# I2C_matrix_V0_1.net
KiCad netlist of a schematic drawn in EAGLE
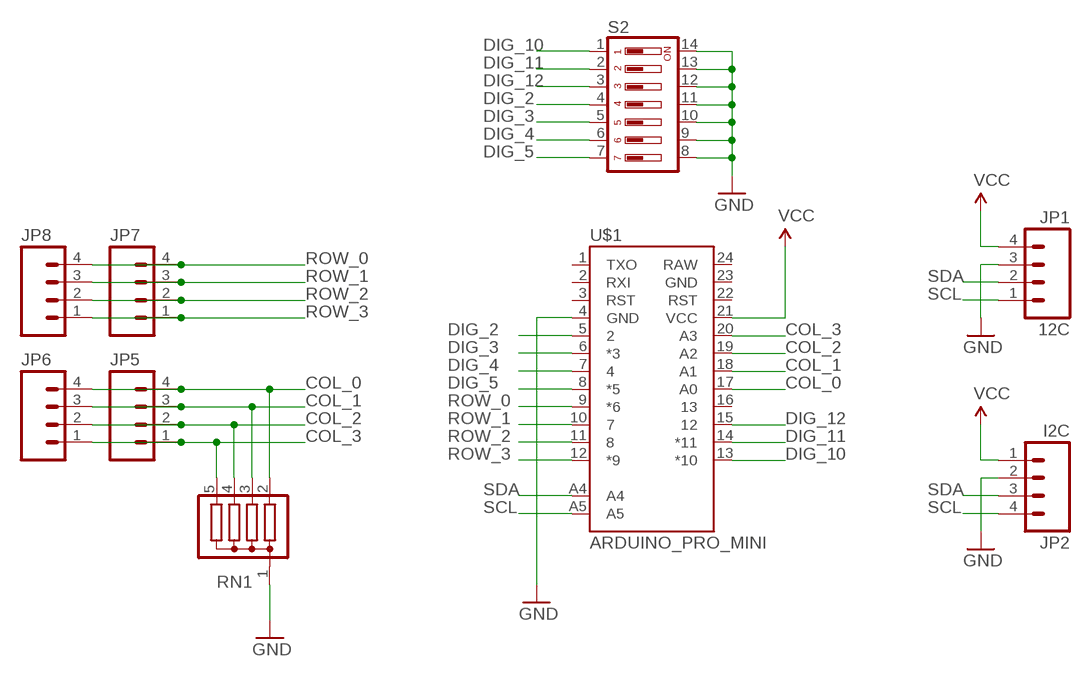
[diagram p0: schematic, sheet 1]

(export (version "E")
  (design (tool "Eeschema 10.0.6"))
  (components
    (comp (ref "JP1")
      (value "12C")
      (footprint "eagle-import:1X04-SMD_LONG")
      (libsource (lib "eagle-import") (part "M04SMD_LONG"))
    )
    (comp (ref "JP2")
      (value "I2C")
      (footprint "eagle-import:1X04-SMD_LONG")
      (libsource (lib "eagle-import") (part "M04SMD_LONG"))
    )
    (comp (ref "JP5")
      (value "M04LONGPADS")
      (footprint "eagle-import:1X04_LONGPADS")
      (libsource (lib "eagle-import") (part "M04LONGPADS"))
    )
    (comp (ref "JP6")
      (value "M04LONGPADS")
      (footprint "eagle-import:1X04_LONGPADS")
      (libsource (lib "eagle-import") (part "M04LONGPADS"))
    )
    (comp (ref "JP7")
      (value "M04LONGPADS")
      (footprint "eagle-import:1X04_LONGPADS")
      (libsource (lib "eagle-import") (part "M04LONGPADS"))
    )
    (comp (ref "JP8")
      (value "M04LONGPADS")
      (footprint "eagle-import:1X04_LONGPADS")
      (libsource (lib "eagle-import") (part "M04LONGPADS"))
    )
    (comp (ref "RN1")
      (value "G04R")
      (footprint "eagle-import:SIL5")
      (libsource (lib "eagle-import") (part "G04R"))
    )
    (comp (ref "S2")
      (value "DIP07YL")
      (footprint "eagle-import:DIP07YL")
      (libsource (lib "eagle-import") (part "DIP07YL"))
    )
    (comp (ref "U$1")
      (value "ARDUINO_PRO_MINI")
      (footprint "eagle-import:ARDUINO_PRO_MINI")
      (libsource (lib "eagle-import") (part "ARDUINO_PRO_MINI"))
    )
  )
  (nets
    (net (code "1") (name "/COL_0") (class "Default")
      (node (ref "JP5") (pin "4") (pinfunction "4_4") (pintype "passive"))
      (node (ref "JP6") (pin "4") (pinfunction "4_4") (pintype "passive"))
      (node (ref "RN1") (pin "2") (pinfunction "2_2") (pintype "passive"))
      (node (ref "U$1") (pin "17") (pinfunction "A0_17") (pintype "bidirectional"))
    )
    (net (code "2") (name "/COL_1") (class "Default")
      (node (ref "JP5") (pin "3") (pinfunction "3_3") (pintype "passive"))
      (node (ref "JP6") (pin "3") (pinfunction "3_3") (pintype "passive"))
      (node (ref "RN1") (pin "3") (pinfunction "3_3") (pintype "passive"))
      (node (ref "U$1") (pin "18") (pinfunction "A1_18") (pintype "bidirectional"))
    )
    (net (code "3") (name "/COL_2") (class "Default")
      (node (ref "JP5") (pin "2") (pinfunction "2_2") (pintype "passive"))
      (node (ref "JP6") (pin "2") (pinfunction "2_2") (pintype "passive"))
      (node (ref "RN1") (pin "4") (pinfunction "4_4") (pintype "passive"))
      (node (ref "U$1") (pin "19") (pinfunction "A2_19") (pintype "bidirectional"))
    )
    (net (code "4") (name "/COL_3") (class "Default")
      (node (ref "JP5") (pin "1") (pinfunction "1_1") (pintype "passive"))
      (node (ref "JP6") (pin "1") (pinfunction "1_1") (pintype "passive"))
      (node (ref "RN1") (pin "5") (pinfunction "5_5") (pintype "passive"))
      (node (ref "U$1") (pin "20") (pinfunction "A3_20") (pintype "bidirectional"))
    )
    (net (code "5") (name "/DIG_2") (class "Default")
      (node (ref "S2") (pin "4") (pinfunction "4_4") (pintype "passive"))
      (node (ref "U$1") (pin "5") (pinfunction "2_5") (pintype "bidirectional"))
    )
    (net (code "6") (name "/DIG_3") (class "Default")
      (node (ref "S2") (pin "5") (pinfunction "5_5") (pintype "passive"))
      (node (ref "U$1") (pin "6") (pinfunction "*3_6") (pintype "bidirectional"))
    )
    (net (code "7") (name "/DIG_4") (class "Default")
      (node (ref "S2") (pin "6") (pinfunction "6_6") (pintype "passive"))
      (node (ref "U$1") (pin "7") (pinfunction "4_7") (pintype "bidirectional"))
    )
    (net (code "8") (name "/DIG_5") (class "Default")
      (node (ref "S2") (pin "7") (pinfunction "7_7") (pintype "passive"))
      (node (ref "U$1") (pin "8") (pinfunction "*5_8") (pintype "bidirectional"))
    )
    (net (code "9") (name "/DIG_10") (class "Default")
      (node (ref "S2") (pin "1") (pinfunction "1_1") (pintype "passive"))
      (node (ref "U$1") (pin "13") (pinfunction "*10_13") (pintype "bidirectional"))
    )
    (net (code "10") (name "/DIG_11") (class "Default")
      (node (ref "S2") (pin "2") (pinfunction "2_2") (pintype "passive"))
      (node (ref "U$1") (pin "14") (pinfunction "*11_14") (pintype "bidirectional"))
    )
    (net (code "11") (name "/DIG_12") (class "Default")
      (node (ref "S2") (pin "3") (pinfunction "3_3") (pintype "passive"))
      (node (ref "U$1") (pin "15") (pinfunction "12_15") (pintype "bidirectional"))
    )
    (net (code "12") (name "/ROW_0") (class "Default")
      (node (ref "JP7") (pin "4") (pinfunction "4_4") (pintype "passive"))
      (node (ref "JP8") (pin "4") (pinfunction "4_4") (pintype "passive"))
      (node (ref "U$1") (pin "9") (pinfunction "*6_9") (pintype "bidirectional"))
    )
    (net (code "13") (name "/ROW_1") (class "Default")
      (node (ref "JP7") (pin "3") (pinfunction "3_3") (pintype "passive"))
      (node (ref "JP8") (pin "3") (pinfunction "3_3") (pintype "passive"))
      (node (ref "U$1") (pin "10") (pinfunction "7_10") (pintype "bidirectional"))
    )
    (net (code "14") (name "/ROW_2") (class "Default")
      (node (ref "JP7") (pin "2") (pinfunction "2_2") (pintype "passive"))
      (node (ref "JP8") (pin "2") (pinfunction "2_2") (pintype "passive"))
      (node (ref "U$1") (pin "11") (pinfunction "8_11") (pintype "bidirectional"))
    )
    (net (code "15") (name "/ROW_3") (class "Default")
      (node (ref "JP7") (pin "1") (pinfunction "1_1") (pintype "passive"))
      (node (ref "JP8") (pin "1") (pinfunction "1_1") (pintype "passive"))
      (node (ref "U$1") (pin "12") (pinfunction "*9_12") (pintype "bidirectional"))
    )
    (net (code "16") (name "/SCL") (class "Default")
      (node (ref "JP1") (pin "1") (pinfunction "1_1") (pintype "passive"))
      (node (ref "JP2") (pin "4") (pinfunction "4_4") (pintype "passive"))
      (node (ref "U$1") (pin "A5") (pinfunction "A5_A5") (pintype "bidirectional"))
    )
    (net (code "17") (name "/SDA") (class "Default")
      (node (ref "JP1") (pin "2") (pinfunction "2_2") (pintype "passive"))
      (node (ref "JP2") (pin "3") (pinfunction "3_3") (pintype "passive"))
      (node (ref "U$1") (pin "A4") (pinfunction "A4_A4") (pintype "bidirectional"))
    )
    (net (code "18") (name "GND") (class "Default")
      (node (ref "JP1") (pin "3") (pinfunction "3_3") (pintype "passive"))
      (node (ref "JP2") (pin "2") (pinfunction "2_2") (pintype "passive"))
      (node (ref "RN1") (pin "1") (pinfunction "1_1") (pintype "passive"))
      (node (ref "S2") (pin "10") (pinfunction "10_10") (pintype "passive"))
      (node (ref "S2") (pin "11") (pinfunction "11_11") (pintype "passive"))
      (node (ref "S2") (pin "12") (pinfunction "12_12") (pintype "passive"))
      (node (ref "S2") (pin "13") (pinfunction "13_13") (pintype "passive"))
      (node (ref "S2") (pin "14") (pinfunction "14_14") (pintype "passive"))
      (node (ref "S2") (pin "8") (pinfunction "8_8") (pintype "passive"))
      (node (ref "S2") (pin "9") (pinfunction "9_9") (pintype "passive"))
      (node (ref "U$1") (pin "4") (pinfunction "GND_4") (pintype "bidirectional"))
    )
    (net (code "19") (name "VCC") (class "Default")
      (node (ref "JP1") (pin "4") (pinfunction "4_4") (pintype "passive"))
      (node (ref "JP2") (pin "1") (pinfunction "1_1") (pintype "passive"))
      (node (ref "U$1") (pin "21") (pinfunction "VCC_21") (pintype "bidirectional"))
    )
    (net (code "20") (name "unconnected-(U$1-13-Pad16)") (class "Default")
      (node (ref "U$1") (pin "16") (pinfunction "13_16") (pintype "bidirectional"))
    )
    (net (code "21") (name "unconnected-(U$1-GND-Pad23)") (class "Default")
      (node (ref "U$1") (pin "23") (pinfunction "GND_23") (pintype "bidirectional"))
    )
    (net (code "22") (name "unconnected-(U$1-RAW-Pad24)") (class "Default")
      (node (ref "U$1") (pin "24") (pinfunction "RAW_24") (pintype "bidirectional"))
    )
    (net (code "23") (name "unconnected-(U$1-RST-Pad3)") (class "Default")
      (node (ref "U$1") (pin "3") (pinfunction "RST_3") (pintype "bidirectional"))
    )
    (net (code "24") (name "unconnected-(U$1-RST-Pad22)") (class "Default")
      (node (ref "U$1") (pin "22") (pinfunction "RST_22") (pintype "bidirectional"))
    )
    (net (code "25") (name "unconnected-(U$1-RXI-Pad2)") (class "Default")
      (node (ref "U$1") (pin "2") (pinfunction "RXI_2") (pintype "bidirectional"))
    )
    (net (code "26") (name "unconnected-(U$1-TXO-Pad1)") (class "Default")
      (node (ref "U$1") (pin "1") (pinfunction "TXO_1") (pintype "bidirectional"))
    )
  )
)
